# motherboard_2ch_arduino.net
KiCad netlist of a schematic drawn in Altium Designer
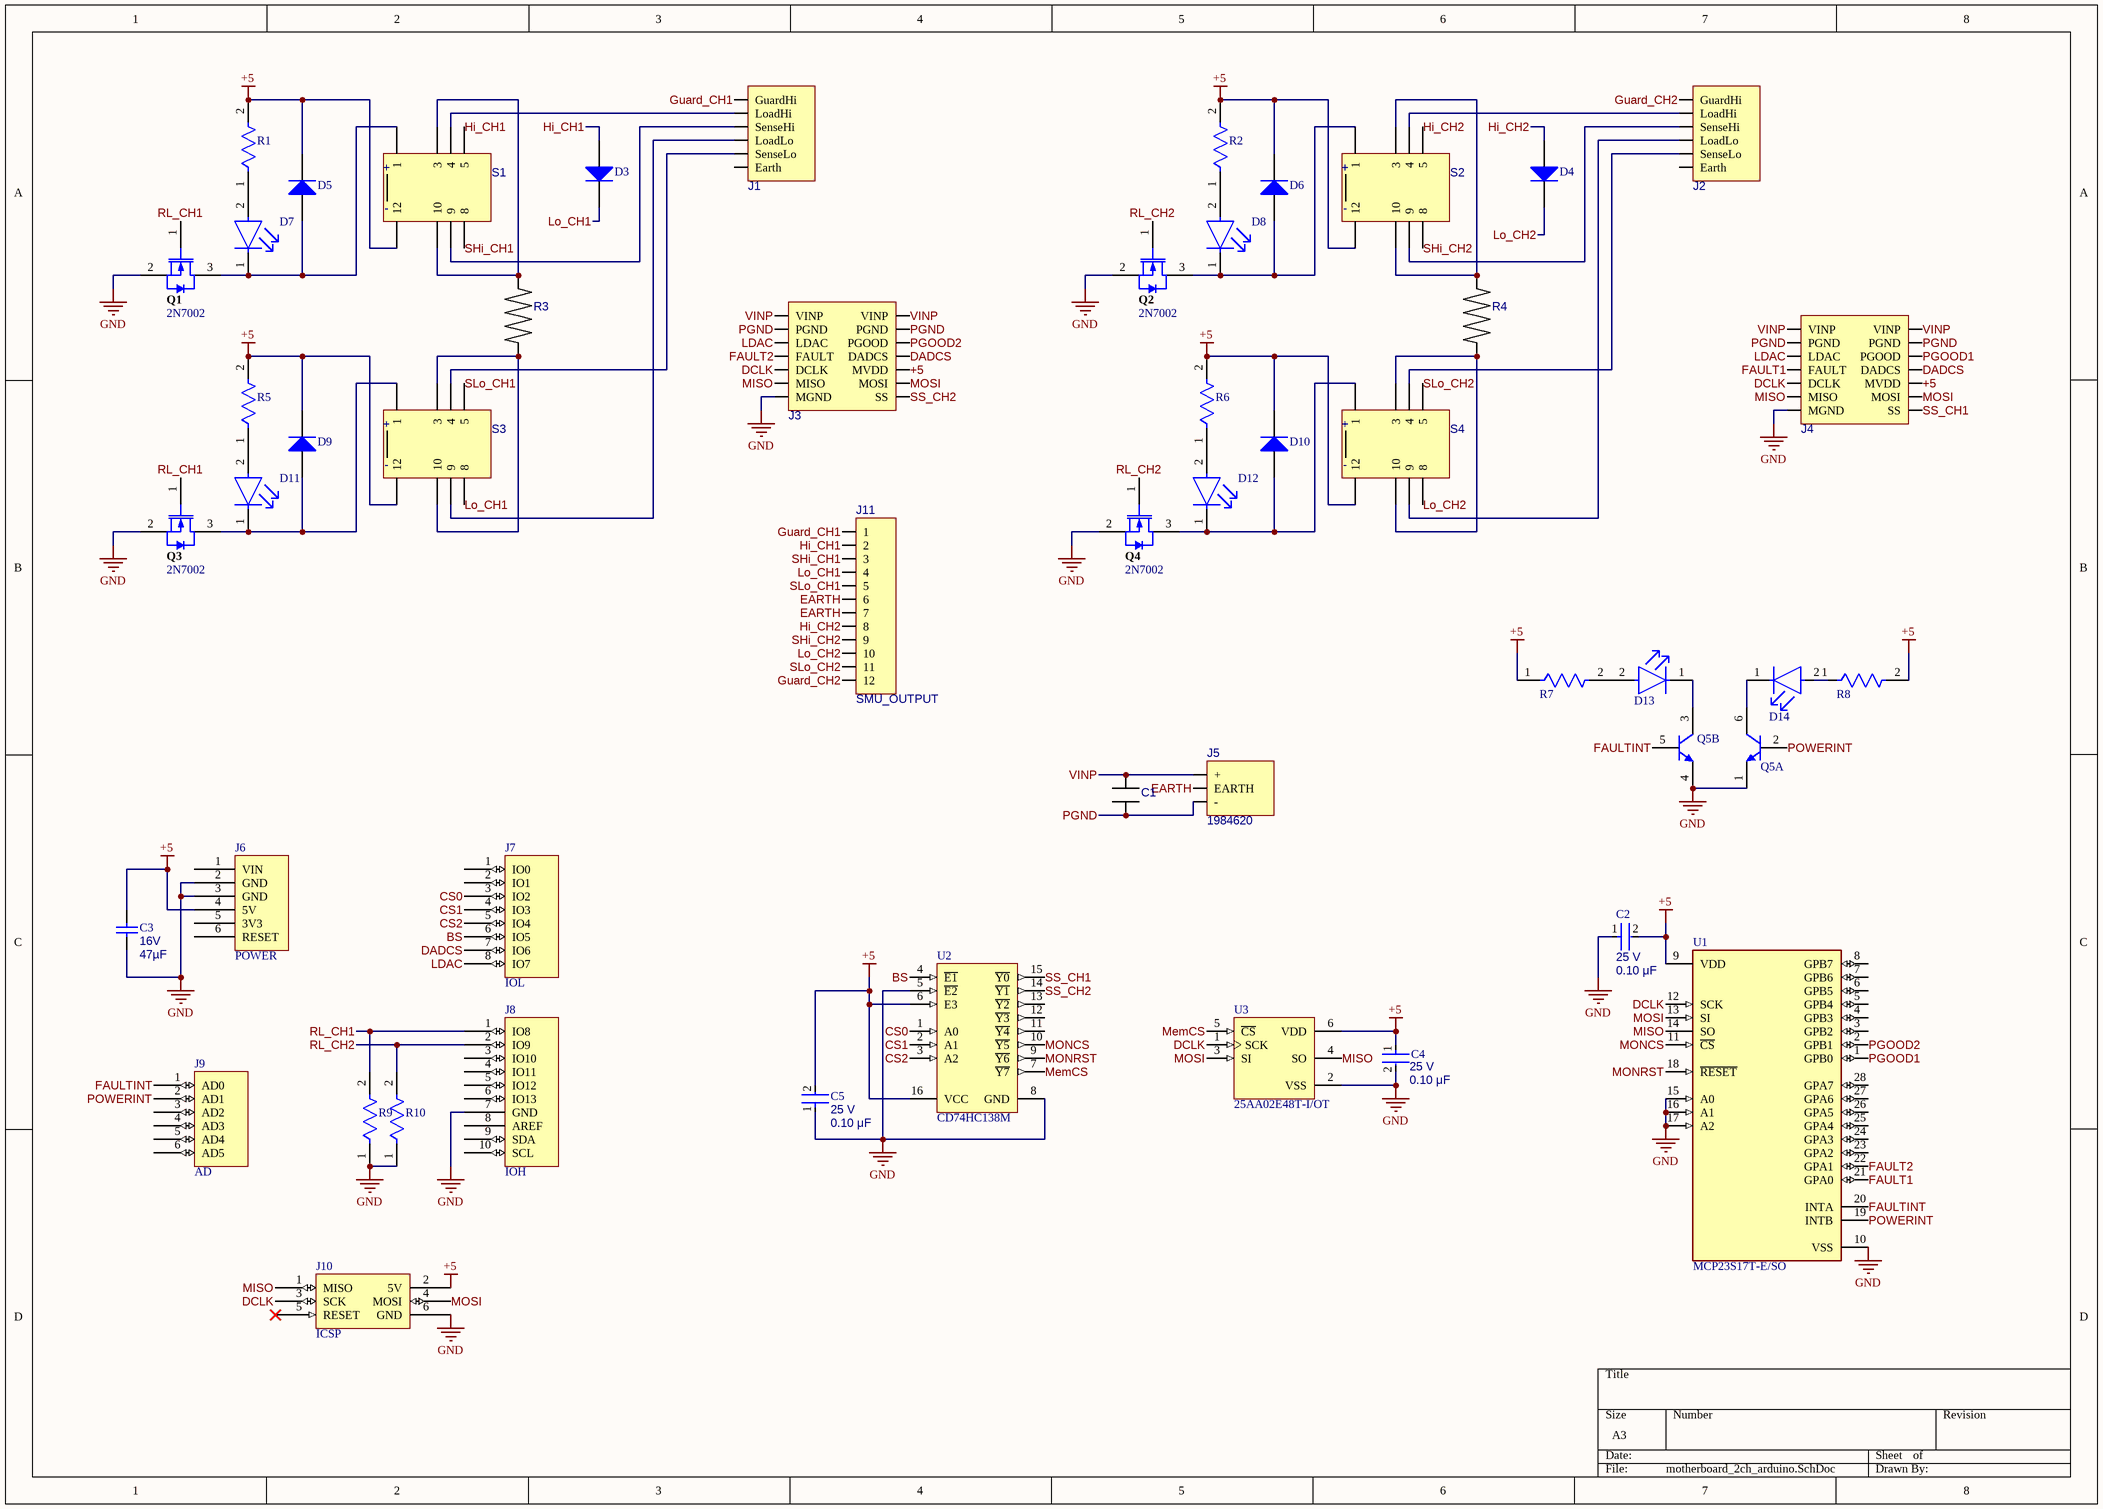
[diagram p0: motherboard_2ch_arduino.SchDoc]

(export (version "E")
  (design (tool "Eeschema 10.0.6"))
  (components
    (comp (ref "C1")
      (value "KRM55TR71H226MH01L")
      (footprint "CAPC6050X50M")
      (libsource (lib "manual") (part "CAP22uF"))
    )
    (comp (ref "C2")
      (value "0.10 μF")
      (footprint "FP-C1206C-EB-IPC_A")
      (description "CAP CER 0.1UF 25V C0G/NP0 1206")
      (fields
        (field (name "VOLTAGE RATING") "25 V")
        (field (name "MANUFACTURER") "KEMET")
        (field (name "TOLERANCE") "0.05")
      )
      (libsource (lib "Altium Content Vault") (part "b4654b650e69147ec39a6b967a45e02"))
    )
    (comp (ref "C3")
      (value "1210YD107MAT2A")
      (footprint "MURA-1210_H_2.7_M")
      (description "Cap Ceramic, 47 uF, +/- 10%, -55 to 85 degC, 2-Pin SMD (1210), RoHS, Tape and Reel")
      (fields
        (field (name "VOLTAGE RATING DC") "16V")
        (field (name "CAPACITANCE") "47µF")
        (field (name "TOLERANCE") "±10%")
        (field (name "MANUFACTURER") "Murata")
      )
      (libsource (lib "Altium Content Vault") (part "CAP-NP-2"))
    )
    (comp (ref "C4")
      (value "0.10 μF")
      (footprint "FP-C1206C-EB-IPC_A")
      (description "CAP CER 0.1UF 25V C0G/NP0 1206")
      (fields
        (field (name "VOLTAGE RATING") "25 V")
        (field (name "MANUFACTURER") "KEMET")
        (field (name "TOLERANCE") "0.05")
      )
      (libsource (lib "Altium Content Vault") (part "b4654b650e69147ec39a6b967a45e02"))
    )
    (comp (ref "C5")
      (value "0.10 μF")
      (footprint "FP-C1206C-EB-IPC_A")
      (description "CAP CER 0.1UF 25V C0G/NP0 1206")
      (fields
        (field (name "VOLTAGE RATING") "25 V")
        (field (name "MANUFACTURER") "KEMET")
        (field (name "TOLERANCE") "0.05")
      )
      (libsource (lib "Altium Content Vault") (part "b4654b650e69147ec39a6b967a45e02"))
    )
    (comp (ref "D3")
      (value "SMAJ33CA-TR")
      (footprint "STM-SMA-2_V")
      (description "Transil(TM) Diode, 33 A, 36.7 V, -55 to 150 degC, 2-Pin SMA, RoHS, Tape and Reel")
      (fields (field (name "MANUFACTURER") "STMicroelectronics"))
      (libsource (lib "Altium Content Vault") (part "D-AK-2"))
    )
    (comp (ref "D4")
      (value "SMAJ33CA-TR")
      (footprint "STM-SMA-2_V")
      (description "Transil(TM) Diode, 33 A, 36.7 V, -55 to 150 degC, 2-Pin SMA, RoHS, Tape and Reel")
      (fields (field (name "MANUFACTURER") "STMicroelectronics"))
      (libsource (lib "Altium Content Vault") (part "D-AK-2"))
    )
    (comp (ref "D5")
      (value "1N4148W-7-F")
      (footprint "DIOD-SOD123-2_V")
      (description "Fast Switching Diode, 100 V, 0.15 A, -65 to 150 degC, 2-Pin?SOD123, RoHS, Tape and Reel")
      (fields (field (name "MANUFACTURER") "DiodesIncorporated"))
      (libsource (lib "Altium Content Vault") (part "D-AK-2"))
    )
    (comp (ref "D6")
      (value "1N4148W-7-F")
      (footprint "DIOD-SOD123-2_V")
      (description "Fast Switching Diode, 100 V, 0.15 A, -65 to 150 degC, 2-Pin?SOD123, RoHS, Tape and Reel")
      (fields (field (name "MANUFACTURER") "DiodesIncorporated"))
      (libsource (lib "Altium Content Vault") (part "D-AK-2"))
    )
    (comp (ref "D7")
      (value "LTST-C150KGKT")
      (footprint "FP-LTST-C150KGKT-MFG")
      (description "LED GREEN CLEAR 1206 SMD")
      (libsource (lib "Altium Content Vault") (part "8706943c75ba83719d021d2fdc84c58"))
    )
    (comp (ref "D8")
      (value "LTST-C150KGKT")
      (footprint "FP-LTST-C150KGKT-MFG")
      (description "LED GREEN CLEAR 1206 SMD")
      (libsource (lib "Altium Content Vault") (part "8706943c75ba83719d021d2fdc84c58"))
    )
    (comp (ref "D9")
      (value "1N4148W-7-F")
      (footprint "DIOD-SOD123-2_V")
      (description "Fast Switching Diode, 100 V, 0.15 A, -65 to 150 degC, 2-Pin?SOD123, RoHS, Tape and Reel")
      (fields (field (name "MANUFACTURER") "DiodesIncorporated"))
      (libsource (lib "Altium Content Vault") (part "D-AK-2"))
    )
    (comp (ref "D10")
      (value "1N4148W-7-F")
      (footprint "DIOD-SOD123-2_V")
      (description "Fast Switching Diode, 100 V, 0.15 A, -65 to 150 degC, 2-Pin?SOD123, RoHS, Tape and Reel")
      (fields (field (name "MANUFACTURER") "DiodesIncorporated"))
      (libsource (lib "Altium Content Vault") (part "D-AK-2"))
    )
    (comp (ref "D11")
      (value "LTST-C150KGKT")
      (footprint "FP-LTST-C150KGKT-MFG")
      (description "LED GREEN CLEAR 1206 SMD")
      (libsource (lib "Altium Content Vault") (part "8706943c75ba83719d021d2fdc84c58"))
    )
    (comp (ref "D12")
      (value "LTST-C150KGKT")
      (footprint "FP-LTST-C150KGKT-MFG")
      (description "LED GREEN CLEAR 1206 SMD")
      (libsource (lib "Altium Content Vault") (part "8706943c75ba83719d021d2fdc84c58"))
    )
    (comp (ref "D13")
      (value "LTST-C150KGKT")
      (footprint "FP-LTST-C150KGKT-MFG")
      (description "LED GREEN CLEAR 1206 SMD")
      (libsource (lib "Altium Content Vault") (part "8706943c75ba83719d021d2fdc84c58"))
    )
    (comp (ref "D14")
      (value "LTST-C150KGKT")
      (footprint "FP-LTST-C150KGKT-MFG")
      (description "LED GREEN CLEAR 1206 SMD")
      (libsource (lib "Altium Content Vault") (part "8706943c75ba83719d021d2fdc84c58"))
    )
    (comp (ref "J1") (value "5-146276-6") (footprint "SMUIO") (libsource (lib "manual") (part "SMUIO_RevB")))
    (comp (ref "J2") (value "5-146276-6") (footprint "SMUIO") (libsource (lib "manual") (part "SMUIO_RevB")))
    (comp (ref "J3") (value "5-146252-7") (footprint "DATAIO") (libsource (lib "manual") (part "DATAIO")))
    (comp (ref "J4") (value "5-146252-7") (footprint "DATAIO") (libsource (lib "manual") (part "DATAIO")))
    (comp (ref "J5") (value "1984620") (footprint "1984620") (libsource (lib "manual") (part "POWERJACK")))
    (comp (ref "J6") (value "POWER") (footprint "Header 6x1 8.5mm") (libsource (lib "Header") (part "POWER")))
    (comp (ref "J7") (value "IOL") (footprint "Header 8x1 8.5mm") (libsource (lib "Header") (part "IOL")))
    (comp (ref "J8") (value "IOH") (footprint "Header 10x1 8.5mm") (libsource (lib "Header") (part "IOH")))
    (comp (ref "J9")
      (value "AD")
      (footprint "Header:Header 6x1 8.5mm")
      (libsource (lib "Header") (part "AD"))
    )
    (comp (ref "J10") (value "ICSP") (footprint "ICSP") (libsource (lib "Header") (part "ICSP")))
    (comp (ref "J11")
      (value "SMU_OUTPUT")
      (footprint "1843897")
      (libsource (lib "Header") (part "SMU_OUTPUT"))
    )
    (comp (ref "Q1")
      (value "2N7002")
      (footprint "INF-PG-SOT23_M")
      (fields (field (name "MANUFACTURER") "Infineon"))
      (libsource (lib "Altium Content Vault") (part "INF-NDMOS-GSD-3"))
    )
    (comp (ref "Q2")
      (value "2N7002")
      (footprint "INF-PG-SOT23_M")
      (fields (field (name "MANUFACTURER") "Infineon"))
      (libsource (lib "Altium Content Vault") (part "INF-NDMOS-GSD-3"))
    )
    (comp (ref "Q3")
      (value "2N7002")
      (footprint "INF-PG-SOT23_M")
      (fields (field (name "MANUFACTURER") "Infineon"))
      (libsource (lib "Altium Content Vault") (part "INF-NDMOS-GSD-3"))
    )
    (comp (ref "Q4")
      (value "2N7002")
      (footprint "INF-PG-SOT23_M")
      (fields (field (name "MANUFACTURER") "Infineon"))
      (libsource (lib "Altium Content Vault") (part "INF-NDMOS-GSD-3"))
    )
    (comp (ref "Q5")
      (value "MBT3904DW1T1G")
      (footprint "ONSC-SOT-363-6-419B-02_W_V")
      (description "Dual General Purpose Transistors, 6-Pin SOT-363, Pb-Free, Tape and Reel")
      (fields (field (name "MANUFACTURER") "On Semiconductor"))
      (libsource (lib "Altium Content Vault") (part "ONSC-NPN_NPN-6_F"))
    )
    (comp (ref "R1")
      (value "RN73R2BTTD1001B25")
      (footprint "FP-RC3216-IPC_A")
      (description "Res Thick Film 1206 1kΩ 5% 0.25W ±100ppm/°C Molded SMD T/R")
      (fields (field (name "TOLERANCE") "5%"))
      (libsource (lib "Altium Content Vault") (part "1029c3af85768c4190bb7ad29bc67b5"))
    )
    (comp (ref "R2")
      (value "RC3216J102CS")
      (footprint "FP-RC3216-IPC_A")
      (description "Res Thick Film 1206 1kΩ 5% 0.25W ±100ppm/°C Molded SMD T/R")
      (fields (field (name "TOLERANCE") "5%"))
      (libsource (lib "Altium Content Vault") (part "1029c3af85768c4190bb7ad29bc67b5"))
    )
    (comp (ref "R3")
      (value "Y1453500R000V9L")
      (footprint "Y1453500R000V9L")
      (libsource (lib "manual") (part "Y1453500R000V9L"))
    )
    (comp (ref "R4")
      (value "Y1453500R000V9L")
      (footprint "Y1453500R000V9L")
      (libsource (lib "manual") (part "Y1453500R000V9L"))
    )
    (comp (ref "R5")
      (value "RC3216J102CS")
      (footprint "FP-RC3216-IPC_A")
      (description "Res Thick Film 1206 1kΩ 5% 0.25W ±100ppm/°C Molded SMD T/R")
      (fields (field (name "TOLERANCE") "5%"))
      (libsource (lib "Altium Content Vault") (part "1029c3af85768c4190bb7ad29bc67b5"))
    )
    (comp (ref "R6")
      (value "RC3216J102CS")
      (footprint "FP-RC3216-IPC_A")
      (description "Res Thick Film 1206 1kΩ 5% 0.25W ±100ppm/°C Molded SMD T/R")
      (fields (field (name "TOLERANCE") "5%"))
      (libsource (lib "Altium Content Vault") (part "1029c3af85768c4190bb7ad29bc67b5"))
    )
    (comp (ref "R7")
      (value "RC3216J102CS")
      (footprint "FP-RC3216-IPC_A")
      (description "Res Thick Film 1206 1kΩ 5% 0.25W ±100ppm/°C Molded SMD T/R")
      (fields (field (name "TOLERANCE") "5%"))
      (libsource (lib "Altium Content Vault") (part "1029c3af85768c4190bb7ad29bc67b5"))
    )
    (comp (ref "R8")
      (value "RC3216J102CS")
      (footprint "FP-RC3216-IPC_A")
      (description "Res Thick Film 1206 1kΩ 5% 0.25W ±100ppm/°C Molded SMD T/R")
      (fields (field (name "TOLERANCE") "5%"))
      (libsource (lib "Altium Content Vault") (part "1029c3af85768c4190bb7ad29bc67b5"))
    )
    (comp (ref "R9")
      (value "RN73H2BTTD1002B10")
      (footprint "FP-RC3216-IPC_A")
      (description "RES SMD 10K OHM 1% 1/4W 1206")
      (fields (field (name "TOLERANCE") "1%"))
      (libsource (lib "Altium Content Vault") (part "1029c3af85768c4190bb7ad29bc67b5"))
    )
    (comp (ref "R10")
      (value "RN73H2BTTD1002B10")
      (footprint "FP-RC3216-IPC_A")
      (description "RES SMD 10K OHM 1% 1/4W 1206")
      (fields (field (name "TOLERANCE") "1%"))
      (libsource (lib "Altium Content Vault") (part "1029c3af85768c4190bb7ad29bc67b5"))
    )
    (comp (ref "S1") (value "G6S-2 DC5") (footprint "EE2-5NU") (libsource (lib "manual") (part "EE2-5NU")))
    (comp (ref "S2") (value "G6S-2 DC5") (footprint "EE2-5NU") (libsource (lib "manual") (part "EE2-5NU")))
    (comp (ref "S3") (value "G6S-2 DC5") (footprint "EE2-5NU") (libsource (lib "manual") (part "EE2-5NU")))
    (comp (ref "S4") (value "G6S-2 DC5") (footprint "EE2-5NU") (libsource (lib "manual") (part "EE2-5NU")))
    (comp (ref "U1")
      (value "MCP23S17T-E/SO")
      (footprint "FP-C04-052-MFG")
      (description "IC I/O EXPANDER SPI 16B 28SOIC")
      (libsource (lib "Altium Content Vault") (part "be0e9b41ae9def86c3880ffea09bd70"))
    )
    (comp (ref "U2")
      (value "CD74HC138M")
      (footprint "D0016A_M")
      (description "High Speed CMOS Logic 3-to-8 Line Decoder Demultiplexer Inverting and Non-Inverting, D0016A, TUBE")
      (fields
        (field (name "MANUFACTURER") "Texas Instruments")
        (field (name "GENERIC PART NUMBER") "CD74HC138")
      )
      (libsource (lib "Altium Content Vault") (part "TI-CDX4HCT138-16"))
    )
    (comp (ref "U3")
      (value "25AA02E48T-I/OT")
      (footprint "SOT-23-OT6_M")
      (libsource (lib "Altium Content Vault") (part "MEM-SEEPROM-25XX0X0A-6"))
    )
  )
  (nets
    (net (code "1") (name "+5") (class "Default")
      (node (ref "C2") (pin "2") (pinfunction "2_2") (pintype "passive"))
      (node (ref "C3") (pin "2") (pinfunction "2_2") (pintype "passive"))
      (node (ref "C4") (pin "1") (pinfunction "1_1") (pintype "passive"))
      (node (ref "C5") (pin "2") (pinfunction "2_2") (pintype "passive"))
      (node (ref "D10") (pin "2") (pinfunction "K_2") (pintype "passive"))
      (node (ref "D5") (pin "2") (pinfunction "K_2") (pintype "passive"))
      (node (ref "D6") (pin "2") (pinfunction "K_2") (pintype "passive"))
      (node (ref "D9") (pin "2") (pinfunction "K_2") (pintype "passive"))
      (node (ref "J10") (pin "2") (pinfunction "5V_2") (pintype "power_in"))
      (node (ref "J3") (pin "10") (pinfunction "MVDD_10") (pintype "passive"))
      (node (ref "J4") (pin "10") (pinfunction "MVDD_10") (pintype "passive"))
      (node (ref "J6") (pin "4") (pinfunction "5V_4") (pintype "power_in"))
      (node (ref "R1") (pin "2") (pinfunction "2_2") (pintype "passive"))
      (node (ref "R2") (pin "2") (pinfunction "2_2") (pintype "passive"))
      (node (ref "R5") (pin "2") (pinfunction "2_2") (pintype "passive"))
      (node (ref "R6") (pin "2") (pinfunction "2_2") (pintype "passive"))
      (node (ref "R7") (pin "1") (pinfunction "1_1") (pintype "passive"))
      (node (ref "R8") (pin "2") (pinfunction "2_2") (pintype "passive"))
      (node (ref "S1") (pin "12") (pinfunction "12_12") (pintype "passive"))
      (node (ref "S2") (pin "12") (pinfunction "12_12") (pintype "passive"))
      (node (ref "S3") (pin "12") (pinfunction "12_12") (pintype "passive"))
      (node (ref "S4") (pin "12") (pinfunction "12_12") (pintype "passive"))
      (node (ref "U1") (pin "9") (pinfunction "VDD_9") (pintype "power_in"))
      (node (ref "U2") (pin "16") (pinfunction "VCC_16") (pintype "power_in"))
      (node (ref "U2") (pin "6") (pinfunction "E3_6") (pintype "input"))
      (node (ref "U3") (pin "6") (pinfunction "VDD_6") (pintype "power_in"))
    )
    (net (code "2") (name "/BS") (class "Default")
      (node (ref "J7") (pin "6") (pinfunction "IO5_6") (pintype "bidirectional"))
      (node (ref "U2") (pin "4") (pinfunction "~{E1}_4") (pintype "input"))
    )
    (net (code "3") (name "/CS0") (class "Default")
      (node (ref "J7") (pin "3") (pinfunction "IO2_3") (pintype "bidirectional"))
      (node (ref "U2") (pin "1") (pinfunction "A0_1") (pintype "input"))
    )
    (net (code "4") (name "/CS1") (class "Default")
      (node (ref "J7") (pin "4") (pinfunction "IO3_4") (pintype "bidirectional"))
      (node (ref "U2") (pin "2") (pinfunction "A1_2") (pintype "input"))
    )
    (net (code "5") (name "/CS2") (class "Default")
      (node (ref "J7") (pin "5") (pinfunction "IO4_5") (pintype "bidirectional"))
      (node (ref "U2") (pin "3") (pinfunction "A2_3") (pintype "input"))
    )
    (net (code "6") (name "/DADCS") (class "Default")
      (node (ref "J3") (pin "8") (pinfunction "DADCS_8") (pintype "passive"))
      (node (ref "J4") (pin "8") (pinfunction "DADCS_8") (pintype "passive"))
      (node (ref "J7") (pin "7") (pinfunction "IO6_7") (pintype "bidirectional"))
    )
    (net (code "7") (name "/DCLK") (class "Default")
      (node (ref "J10") (pin "3") (pinfunction "SCK_3") (pintype "bidirectional"))
      (node (ref "J3") (pin "9") (pinfunction "DCLK_9") (pintype "passive"))
      (node (ref "J4") (pin "9") (pinfunction "DCLK_9") (pintype "passive"))
      (node (ref "U1") (pin "12") (pinfunction "SCK_12") (pintype "input"))
      (node (ref "U3") (pin "1") (pinfunction "SCK_1") (pintype "input"))
    )
    (net (code "8") (name "/EARTH") (class "Default")
      (node (ref "J11") (pin "6") (pinfunction "6_6") (pintype "passive"))
      (node (ref "J11") (pin "7") (pinfunction "7_7") (pintype "passive"))
      (node (ref "J5") (pin "2") (pinfunction "EARTH_2") (pintype "passive"))
    )
    (net (code "9") (name "/FAULT1") (class "Default")
      (node (ref "J4") (pin "7") (pinfunction "FAULT_7") (pintype "passive"))
      (node (ref "U1") (pin "21") (pinfunction "GPA0_21") (pintype "bidirectional"))
    )
    (net (code "10") (name "/FAULT2") (class "Default")
      (node (ref "J3") (pin "7") (pinfunction "FAULT_7") (pintype "passive"))
      (node (ref "U1") (pin "22") (pinfunction "GPA1_22") (pintype "bidirectional"))
    )
    (net (code "11") (name "/FAULTINT") (class "Default")
      (node (ref "J9") (pin "1") (pinfunction "AD0_1") (pintype "bidirectional"))
      (node (ref "Q5") (pin "5") (pinfunction "B_5") (pintype "passive"))
      (node (ref "U1") (pin "20") (pinfunction "INTA_20") (pintype "open_collector"))
    )
    (net (code "12") (name "/Guard_CH1") (class "Default")
      (node (ref "J1") (pin "1") (pinfunction "GuardHi_1") (pintype "passive"))
      (node (ref "J11") (pin "1") (pinfunction "1_1") (pintype "passive"))
    )
    (net (code "13") (name "/Guard_CH2") (class "Default")
      (node (ref "J11") (pin "12") (pinfunction "12_12") (pintype "passive"))
      (node (ref "J2") (pin "1") (pinfunction "GuardHi_1") (pintype "passive"))
    )
    (net (code "14") (name "/Hi_CH1") (class "Default")
      (node (ref "D3") (pin "1") (pinfunction "A_1") (pintype "passive"))
      (node (ref "J11") (pin "2") (pinfunction "2_2") (pintype "passive"))
      (node (ref "S1") (pin "5") (pinfunction "5_5") (pintype "passive"))
    )
    (net (code "15") (name "/Hi_CH2") (class "Default")
      (node (ref "D4") (pin "1") (pinfunction "A_1") (pintype "passive"))
      (node (ref "J11") (pin "8") (pinfunction "8_8") (pintype "passive"))
      (node (ref "S2") (pin "5") (pinfunction "5_5") (pintype "passive"))
    )
    (net (code "16") (name "/LDAC") (class "Default")
      (node (ref "J3") (pin "5") (pinfunction "LDAC_5") (pintype "passive"))
      (node (ref "J4") (pin "5") (pinfunction "LDAC_5") (pintype "passive"))
      (node (ref "J7") (pin "8") (pinfunction "IO7_8") (pintype "bidirectional"))
    )
    (net (code "17") (name "/Lo_CH1") (class "Default")
      (node (ref "D3") (pin "2") (pinfunction "K_2") (pintype "passive"))
      (node (ref "J11") (pin "4") (pinfunction "4_4") (pintype "passive"))
      (node (ref "S3") (pin "8") (pinfunction "8_8") (pintype "passive"))
    )
    (net (code "18") (name "/Lo_CH2") (class "Default")
      (node (ref "D4") (pin "2") (pinfunction "K_2") (pintype "passive"))
      (node (ref "J11") (pin "10") (pinfunction "10_10") (pintype "passive"))
      (node (ref "S4") (pin "8") (pinfunction "8_8") (pintype "passive"))
    )
    (net (code "19") (name "/MISO") (class "Default")
      (node (ref "J10") (pin "1") (pinfunction "MISO_1") (pintype "bidirectional"))
      (node (ref "J3") (pin "11") (pinfunction "MISO_11") (pintype "passive"))
      (node (ref "J4") (pin "11") (pinfunction "MISO_11") (pintype "passive"))
      (node (ref "U1") (pin "14") (pinfunction "SO_14") (pintype "tri_state"))
      (node (ref "U3") (pin "4") (pinfunction "SO_4") (pintype "tri_state"))
    )
    (net (code "20") (name "/MONCS") (class "Default")
      (node (ref "U1") (pin "11") (pinfunction "~{CS}_11") (pintype "input"))
      (node (ref "U2") (pin "10") (pinfunction "~{Y5}_10") (pintype "output"))
    )
    (net (code "21") (name "/MONRST") (class "Default")
      (node (ref "U1") (pin "18") (pinfunction "~{RESET}_18") (pintype "input"))
      (node (ref "U2") (pin "9") (pinfunction "~{Y6}_9") (pintype "output"))
    )
    (net (code "22") (name "/MOSI") (class "Default")
      (node (ref "J10") (pin "4") (pinfunction "MOSI_4") (pintype "bidirectional"))
      (node (ref "J3") (pin "12") (pinfunction "MOSI_12") (pintype "passive"))
      (node (ref "J4") (pin "12") (pinfunction "MOSI_12") (pintype "passive"))
      (node (ref "U1") (pin "13") (pinfunction "SI_13") (pintype "input"))
      (node (ref "U3") (pin "3") (pinfunction "SI_3") (pintype "input"))
    )
    (net (code "23") (name "/MemCS") (class "Default")
      (node (ref "U2") (pin "7") (pinfunction "~{Y7}_7") (pintype "output"))
      (node (ref "U3") (pin "5") (pinfunction "~{CS}_5") (pintype "input"))
    )
    (net (code "24") (name "/PGND") (class "Default")
      (node (ref "C1") (pin "1") (pintype "passive"))
      (node (ref "J3") (pin "3") (pinfunction "PGND_3") (pintype "passive"))
      (node (ref "J3") (pin "4") (pinfunction "PGND_4") (pintype "passive"))
      (node (ref "J4") (pin "3") (pinfunction "PGND_3") (pintype "passive"))
      (node (ref "J4") (pin "4") (pinfunction "PGND_4") (pintype "passive"))
      (node (ref "J5") (pin "3") (pinfunction "-_3") (pintype "passive"))
    )
    (net (code "25") (name "/PGOOD1") (class "Default")
      (node (ref "J4") (pin "6") (pinfunction "PGOOD_6") (pintype "passive"))
      (node (ref "U1") (pin "1") (pinfunction "GPB0_1") (pintype "bidirectional"))
    )
    (net (code "26") (name "/PGOOD2") (class "Default")
      (node (ref "J3") (pin "6") (pinfunction "PGOOD_6") (pintype "passive"))
      (node (ref "U1") (pin "2") (pinfunction "GPB1_2") (pintype "bidirectional"))
    )
    (net (code "27") (name "/POWERINT") (class "Default")
      (node (ref "J9") (pin "2") (pinfunction "AD1_2") (pintype "bidirectional"))
      (node (ref "Q5") (pin "2") (pinfunction "B_2") (pintype "passive"))
      (node (ref "U1") (pin "19") (pinfunction "INTB_19") (pintype "open_collector"))
    )
    (net (code "28") (name "/RL_CH1") (class "Default")
      (node (ref "J8") (pin "1") (pinfunction "IO8_1") (pintype "bidirectional"))
      (node (ref "Q1") (pin "1") (pinfunction "GATE_1") (pintype "passive"))
      (node (ref "Q3") (pin "1") (pinfunction "GATE_1") (pintype "passive"))
      (node (ref "R9") (pin "2") (pinfunction "2_2") (pintype "passive"))
    )
    (net (code "29") (name "/RL_CH2") (class "Default")
      (node (ref "J8") (pin "2") (pinfunction "IO9_2") (pintype "bidirectional"))
      (node (ref "Q2") (pin "1") (pinfunction "GATE_1") (pintype "passive"))
      (node (ref "Q4") (pin "1") (pinfunction "GATE_1") (pintype "passive"))
      (node (ref "R10") (pin "2") (pinfunction "2_2") (pintype "passive"))
    )
    (net (code "30") (name "/SHi_CH1") (class "Default")
      (node (ref "J11") (pin "3") (pinfunction "3_3") (pintype "passive"))
      (node (ref "S1") (pin "8") (pinfunction "8_8") (pintype "passive"))
    )
    (net (code "31") (name "/SHi_CH2") (class "Default")
      (node (ref "J11") (pin "9") (pinfunction "9_9") (pintype "passive"))
      (node (ref "S2") (pin "8") (pinfunction "8_8") (pintype "passive"))
    )
    (net (code "32") (name "/SLo_CH1") (class "Default")
      (node (ref "J11") (pin "5") (pinfunction "5_5") (pintype "passive"))
      (node (ref "S3") (pin "5") (pinfunction "5_5") (pintype "passive"))
    )
    (net (code "33") (name "/SLo_CH2") (class "Default")
      (node (ref "J11") (pin "11") (pinfunction "11_11") (pintype "passive"))
      (node (ref "S4") (pin "5") (pinfunction "5_5") (pintype "passive"))
    )
    (net (code "34") (name "/SS_CH1") (class "Default")
      (node (ref "J4") (pin "14") (pinfunction "SS_14") (pintype "passive"))
      (node (ref "U2") (pin "15") (pinfunction "~{Y0}_15") (pintype "output"))
    )
    (net (code "35") (name "/SS_CH2") (class "Default")
      (node (ref "J3") (pin "14") (pinfunction "SS_14") (pintype "passive"))
      (node (ref "U2") (pin "14") (pinfunction "~{Y1}_14") (pintype "output"))
    )
    (net (code "36") (name "/VINP") (class "Default")
      (node (ref "C1") (pin "2") (pintype "passive"))
      (node (ref "J3") (pin "1") (pinfunction "VINP_1") (pintype "passive"))
      (node (ref "J3") (pin "2") (pinfunction "VINP_2") (pintype "passive"))
      (node (ref "J4") (pin "1") (pinfunction "VINP_1") (pintype "passive"))
      (node (ref "J4") (pin "2") (pinfunction "VINP_2") (pintype "passive"))
      (node (ref "J5") (pin "1") (pinfunction "+_1") (pintype "passive"))
    )
    (net (code "37") (name "GND") (class "Default")
      (node (ref "C2") (pin "1") (pinfunction "1_1") (pintype "passive"))
      (node (ref "C3") (pin "1") (pinfunction "1_1") (pintype "passive"))
      (node (ref "C4") (pin "2") (pinfunction "2_2") (pintype "passive"))
      (node (ref "C5") (pin "1") (pinfunction "1_1") (pintype "passive"))
      (node (ref "J10") (pin "6") (pinfunction "GND_6") (pintype "power_in"))
      (node (ref "J3") (pin "13") (pinfunction "MGND_13") (pintype "passive"))
      (node (ref "J4") (pin "13") (pinfunction "MGND_13") (pintype "passive"))
      (node (ref "J6") (pin "2") (pinfunction "GND_2") (pintype "power_in"))
      (node (ref "J6") (pin "3") (pinfunction "GND_3") (pintype "power_in"))
      (node (ref "J8") (pin "7") (pinfunction "GND_7") (pintype "power_in"))
      (node (ref "Q1") (pin "2") (pinfunction "SOURCE_2") (pintype "passive"))
      (node (ref "Q2") (pin "2") (pinfunction "SOURCE_2") (pintype "passive"))
      (node (ref "Q3") (pin "2") (pinfunction "SOURCE_2") (pintype "passive"))
      (node (ref "Q4") (pin "2") (pinfunction "SOURCE_2") (pintype "passive"))
      (node (ref "Q5") (pin "1") (pinfunction "E_1") (pintype "passive"))
      (node (ref "Q5") (pin "4") (pinfunction "E_4") (pintype "passive"))
      (node (ref "R10") (pin "1") (pinfunction "1_1") (pintype "passive"))
      (node (ref "R9") (pin "1") (pinfunction "1_1") (pintype "passive"))
      (node (ref "U1") (pin "10") (pinfunction "VSS_10") (pintype "power_in"))
      (node (ref "U1") (pin "15") (pinfunction "A0_15") (pintype "input"))
      (node (ref "U1") (pin "16") (pinfunction "A1_16") (pintype "input"))
      (node (ref "U1") (pin "17") (pinfunction "A2_17") (pintype "input"))
      (node (ref "U2") (pin "5") (pinfunction "~{E2}_5") (pintype "input"))
      (node (ref "U2") (pin "8") (pinfunction "GND_8") (pintype "power_in"))
      (node (ref "U3") (pin "2") (pinfunction "VSS_2") (pintype "power_in"))
    )
    (net (code "38") (name "Net-(D5-A)") (class "Default")
      (node (ref "D5") (pin "1") (pinfunction "A_1") (pintype "passive"))
      (node (ref "D7") (pin "1") (pinfunction "C_1") (pintype "passive"))
      (node (ref "Q1") (pin "3") (pinfunction "DRAIN_3") (pintype "passive"))
      (node (ref "S1") (pin "1") (pinfunction "1_1") (pintype "passive"))
    )
    (net (code "39") (name "Net-(D6-A)") (class "Default")
      (node (ref "D6") (pin "1") (pinfunction "A_1") (pintype "passive"))
      (node (ref "D8") (pin "1") (pinfunction "C_1") (pintype "passive"))
      (node (ref "Q2") (pin "3") (pinfunction "DRAIN_3") (pintype "passive"))
      (node (ref "S2") (pin "1") (pinfunction "1_1") (pintype "passive"))
    )
    (net (code "40") (name "Net-(D7-A)") (class "Default")
      (node (ref "D7") (pin "2") (pinfunction "A_2") (pintype "passive"))
      (node (ref "R1") (pin "1") (pinfunction "1_1") (pintype "passive"))
    )
    (net (code "41") (name "Net-(D8-A)") (class "Default")
      (node (ref "D8") (pin "2") (pinfunction "A_2") (pintype "passive"))
      (node (ref "R2") (pin "1") (pinfunction "1_1") (pintype "passive"))
    )
    (net (code "42") (name "Net-(D10-A)") (class "Default")
      (node (ref "D10") (pin "1") (pinfunction "A_1") (pintype "passive"))
      (node (ref "D12") (pin "1") (pinfunction "C_1") (pintype "passive"))
      (node (ref "Q4") (pin "3") (pinfunction "DRAIN_3") (pintype "passive"))
      (node (ref "S4") (pin "1") (pinfunction "1_1") (pintype "passive"))
    )
    (net (code "43") (name "Net-(D11-A)") (class "Default")
      (node (ref "D11") (pin "2") (pinfunction "A_2") (pintype "passive"))
      (node (ref "R5") (pin "1") (pinfunction "1_1") (pintype "passive"))
    )
    (net (code "44") (name "Net-(D11-C)") (class "Default")
      (node (ref "D11") (pin "1") (pinfunction "C_1") (pintype "passive"))
      (node (ref "D9") (pin "1") (pinfunction "A_1") (pintype "passive"))
      (node (ref "Q3") (pin "3") (pinfunction "DRAIN_3") (pintype "passive"))
      (node (ref "S3") (pin "1") (pinfunction "1_1") (pintype "passive"))
    )
    (net (code "45") (name "Net-(D12-A)") (class "Default")
      (node (ref "D12") (pin "2") (pinfunction "A_2") (pintype "passive"))
      (node (ref "R6") (pin "1") (pinfunction "1_1") (pintype "passive"))
    )
    (net (code "46") (name "Net-(D13-A)") (class "Default")
      (node (ref "D13") (pin "2") (pinfunction "A_2") (pintype "passive"))
      (node (ref "R7") (pin "2") (pinfunction "2_2") (pintype "passive"))
    )
    (net (code "47") (name "Net-(D13-C)") (class "Default")
      (node (ref "D13") (pin "1") (pinfunction "C_1") (pintype "passive"))
      (node (ref "Q5") (pin "3") (pinfunction "C_3") (pintype "passive"))
    )
    (net (code "48") (name "Net-(D14-A)") (class "Default")
      (node (ref "D14") (pin "2") (pinfunction "A_2") (pintype "passive"))
      (node (ref "R8") (pin "1") (pinfunction "1_1") (pintype "passive"))
    )
    (net (code "49") (name "Net-(D14-C)") (class "Default")
      (node (ref "D14") (pin "1") (pinfunction "C_1") (pintype "passive"))
      (node (ref "Q5") (pin "6") (pinfunction "C_6") (pintype "passive"))
    )
    (net (code "50") (name "Net-(J1-LoadHi)") (class "Default")
      (node (ref "J1") (pin "2") (pinfunction "LoadHi_2") (pintype "passive"))
      (node (ref "S1") (pin "4") (pinfunction "4_4") (pintype "passive"))
    )
    (net (code "51") (name "Net-(J1-LoadLo)") (class "Default")
      (node (ref "J1") (pin "4") (pinfunction "LoadLo_4") (pintype "passive"))
      (node (ref "S3") (pin "9") (pinfunction "9_9") (pintype "passive"))
    )
    (net (code "52") (name "Net-(J1-SenseHi)") (class "Default")
      (node (ref "J1") (pin "3") (pinfunction "SenseHi_3") (pintype "passive"))
      (node (ref "S1") (pin "9") (pinfunction "9_9") (pintype "passive"))
    )
    (net (code "53") (name "Net-(J1-SenseLo)") (class "Default")
      (node (ref "J1") (pin "5") (pinfunction "SenseLo_5") (pintype "passive"))
      (node (ref "S3") (pin "4") (pinfunction "4_4") (pintype "passive"))
    )
    (net (code "54") (name "Net-(J2-LoadHi)") (class "Default")
      (node (ref "J2") (pin "2") (pinfunction "LoadHi_2") (pintype "passive"))
      (node (ref "S2") (pin "4") (pinfunction "4_4") (pintype "passive"))
    )
    (net (code "55") (name "Net-(J2-LoadLo)") (class "Default")
      (node (ref "J2") (pin "4") (pinfunction "LoadLo_4") (pintype "passive"))
      (node (ref "S4") (pin "9") (pinfunction "9_9") (pintype "passive"))
    )
    (net (code "56") (name "Net-(J2-SenseHi)") (class "Default")
      (node (ref "J2") (pin "3") (pinfunction "SenseHi_3") (pintype "passive"))
      (node (ref "S2") (pin "9") (pinfunction "9_9") (pintype "passive"))
    )
    (net (code "57") (name "Net-(J2-SenseLo)") (class "Default")
      (node (ref "J2") (pin "5") (pinfunction "SenseLo_5") (pintype "passive"))
      (node (ref "S4") (pin "4") (pinfunction "4_4") (pintype "passive"))
    )
    (net (code "58") (name "Net-(R3-Pad1)") (class "Default")
      (node (ref "R3") (pin "1") (pinfunction "1_1") (pintype "passive"))
      (node (ref "S3") (pin "10") (pinfunction "10_10") (pintype "passive"))
      (node (ref "S3") (pin "3") (pinfunction "3_3") (pintype "passive"))
    )
    (net (code "59") (name "Net-(R3-Pad2)") (class "Default")
      (node (ref "R3") (pin "2") (pinfunction "2_2") (pintype "passive"))
      (node (ref "S1") (pin "10") (pinfunction "10_10") (pintype "passive"))
      (node (ref "S1") (pin "3") (pinfunction "3_3") (pintype "passive"))
    )
    (net (code "60") (name "Net-(R4-Pad1)") (class "Default")
      (node (ref "R4") (pin "1") (pinfunction "1_1") (pintype "passive"))
      (node (ref "S4") (pin "10") (pinfunction "10_10") (pintype "passive"))
      (node (ref "S4") (pin "3") (pinfunction "3_3") (pintype "passive"))
    )
    (net (code "61") (name "Net-(R4-Pad2)") (class "Default")
      (node (ref "R4") (pin "2") (pinfunction "2_2") (pintype "passive"))
      (node (ref "S2") (pin "10") (pinfunction "10_10") (pintype "passive"))
      (node (ref "S2") (pin "3") (pinfunction "3_3") (pintype "passive"))
    )
    (net (code "62") (name "unconnected-(J1-Earth-Pad6)") (class "Default")
      (node (ref "J1") (pin "6") (pinfunction "Earth_6") (pintype "passive"))
    )
    (net (code "63") (name "unconnected-(J2-Earth-Pad6)") (class "Default")
      (node (ref "J2") (pin "6") (pinfunction "Earth_6") (pintype "passive"))
    )
    (net (code "64") (name "unconnected-(J6-3V3-Pad5)") (class "Default")
      (node (ref "J6") (pin "5") (pinfunction "3V3_5") (pintype "power_in"))
    )
    (net (code "65") (name "unconnected-(J6-RESET-Pad6)") (class "Default")
      (node (ref "J6") (pin "6") (pinfunction "RESET_6") (pintype "passive"))
    )
    (net (code "66") (name "unconnected-(J6-VIN-Pad1)") (class "Default")
      (node (ref "J6") (pin "1") (pinfunction "VIN_1") (pintype "power_in"))
    )
    (net (code "67") (name "unconnected-(J7-IO0-Pad1)") (class "Default")
      (node (ref "J7") (pin "1") (pinfunction "IO0_1") (pintype "bidirectional"))
    )
    (net (code "68") (name "unconnected-(J7-IO1-Pad2)") (class "Default")
      (node (ref "J7") (pin "2") (pinfunction "IO1_2") (pintype "bidirectional"))
    )
    (net (code "69") (name "unconnected-(J8-AREF-Pad8)") (class "Default")
      (node (ref "J8") (pin "8") (pinfunction "AREF_8") (pintype "passive"))
    )
    (net (code "70") (name "unconnected-(J8-IO10-Pad3)") (class "Default")
      (node (ref "J8") (pin "3") (pinfunction "IO10_3") (pintype "bidirectional"))
    )
    (net (code "71") (name "unconnected-(J8-IO11-Pad4)") (class "Default")
      (node (ref "J8") (pin "4") (pinfunction "IO11_4") (pintype "bidirectional"))
    )
    (net (code "72") (name "unconnected-(J8-IO12-Pad5)") (class "Default")
      (node (ref "J8") (pin "5") (pinfunction "IO12_5") (pintype "bidirectional"))
    )
    (net (code "73") (name "unconnected-(J8-IO13-Pad6)") (class "Default")
      (node (ref "J8") (pin "6") (pinfunction "IO13_6") (pintype "bidirectional"))
    )
    (net (code "74") (name "unconnected-(J8-SCL-Pad10)") (class "Default")
      (node (ref "J8") (pin "10") (pinfunction "SCL_10") (pintype "bidirectional"))
    )
    (net (code "75") (name "unconnected-(J8-SDA-Pad9)") (class "Default")
      (node (ref "J8") (pin "9") (pinfunction "SDA_9") (pintype "bidirectional"))
    )
    (net (code "76") (name "unconnected-(J9-AD2-Pad3)") (class "Default")
      (node (ref "J9") (pin "3") (pinfunction "AD2_3") (pintype "bidirectional"))
    )
    (net (code "77") (name "unconnected-(J9-AD3-Pad4)") (class "Default")
      (node (ref "J9") (pin "4") (pinfunction "AD3_4") (pintype "bidirectional"))
    )
    (net (code "78") (name "unconnected-(J9-AD4-Pad5)") (class "Default")
      (node (ref "J9") (pin "5") (pinfunction "AD4_5") (pintype "bidirectional"))
    )
    (net (code "79") (name "unconnected-(J9-AD5-Pad6)") (class "Default")
      (node (ref "J9") (pin "6") (pinfunction "AD5_6") (pintype "bidirectional"))
    )
    (net (code "80") (name "unconnected-(J10-RESET-Pad5)") (class "Default")
      (node (ref "J10") (pin "5") (pinfunction "RESET_5") (pintype "input+no_connect"))
    )
    (net (code "81") (name "unconnected-(U1-GPA2-Pad23)") (class "Default")
      (node (ref "U1") (pin "23") (pinfunction "GPA2_23") (pintype "bidirectional"))
    )
    (net (code "82") (name "unconnected-(U1-GPA3-Pad24)") (class "Default")
      (node (ref "U1") (pin "24") (pinfunction "GPA3_24") (pintype "bidirectional"))
    )
    (net (code "83") (name "unconnected-(U1-GPA4-Pad25)") (class "Default")
      (node (ref "U1") (pin "25") (pinfunction "GPA4_25") (pintype "bidirectional"))
    )
    (net (code "84") (name "unconnected-(U1-GPA5-Pad26)") (class "Default")
      (node (ref "U1") (pin "26") (pinfunction "GPA5_26") (pintype "bidirectional"))
    )
    (net (code "85") (name "unconnected-(U1-GPA6-Pad27)") (class "Default")
      (node (ref "U1") (pin "27") (pinfunction "GPA6_27") (pintype "bidirectional"))
    )
    (net (code "86") (name "unconnected-(U1-GPA7-Pad28)") (class "Default")
      (node (ref "U1") (pin "28") (pinfunction "GPA7_28") (pintype "bidirectional"))
    )
    (net (code "87") (name "unconnected-(U1-GPB2-Pad3)") (class "Default")
      (node (ref "U1") (pin "3") (pinfunction "GPB2_3") (pintype "bidirectional"))
    )
    (net (code "88") (name "unconnected-(U1-GPB3-Pad4)") (class "Default")
      (node (ref "U1") (pin "4") (pinfunction "GPB3_4") (pintype "bidirectional"))
    )
    (net (code "89") (name "unconnected-(U1-GPB4-Pad5)") (class "Default")
      (node (ref "U1") (pin "5") (pinfunction "GPB4_5") (pintype "bidirectional"))
    )
    (net (code "90") (name "unconnected-(U1-GPB5-Pad6)") (class "Default")
      (node (ref "U1") (pin "6") (pinfunction "GPB5_6") (pintype "bidirectional"))
    )
    (net (code "91") (name "unconnected-(U1-GPB6-Pad7)") (class "Default")
      (node (ref "U1") (pin "7") (pinfunction "GPB6_7") (pintype "bidirectional"))
    )
    (net (code "92") (name "unconnected-(U1-GPB7-Pad8)") (class "Default")
      (node (ref "U1") (pin "8") (pinfunction "GPB7_8") (pintype "bidirectional"))
    )
    (net (code "93") (name "unconnected-(U2-~{Y2}-Pad13)") (class "Default")
      (node (ref "U2") (pin "13") (pinfunction "~{Y2}_13") (pintype "output"))
    )
    (net (code "94") (name "unconnected-(U2-~{Y3}-Pad12)") (class "Default")
      (node (ref "U2") (pin "12") (pinfunction "~{Y3}_12") (pintype "output"))
    )
    (net (code "95") (name "unconnected-(U2-~{Y4}-Pad11)") (class "Default")
      (node (ref "U2") (pin "11") (pinfunction "~{Y4}_11") (pintype "output"))
    )
  )
)
